# GT_16u2_Rev2.net
KiCad netlist of a schematic drawn in Altium Designer
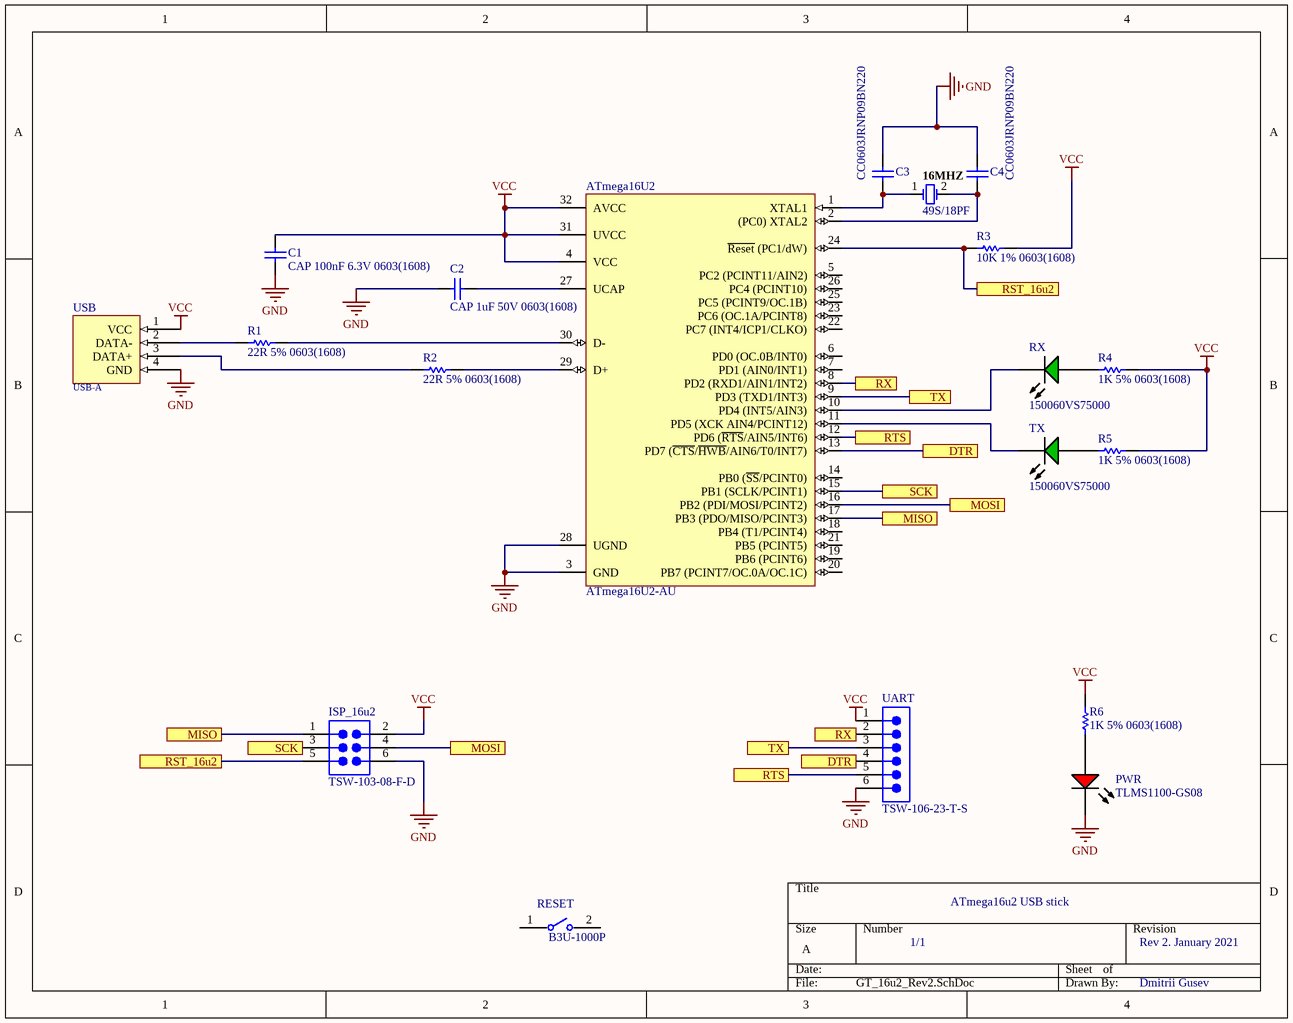
[diagram p0: GT_16u2_Rev2.SchDoc]

(export (version "E")
  (design (tool "Eeschema 10.0.6"))
  (components
    (comp (ref "16MHZ")
      (value "49S/18PF")
      (footprint "JPY-49S-18PF")
      (description "Crystal, 16 MHz, 18 pF, -20 to 70 degC, 2-Pin THD")
      (fields (field (name "MANUFACTURER") "Shenzhen Jingpengyuan"))
      (libsource (lib "Altium Content Vault") (part "XTAL-1-2-2"))
    )
    (comp (ref "ATmega16U2")
      (value "ATmega16U2-AU")
      (footprint "32A_M")
      (libsource (lib "Altium Content Vault") (part "MC-8B-ATM8U2-SQ32"))
    )
    (comp (ref "C1")
      (value "CAP 100nF 6.3V 0603(1608)")
      (footprint "CAPC0603(1608)100_L")
      (description "CAP 100nF 6.3V ±20% 0603 (1608 Metric) Thickness 1mm SMD")
      (fields (field (name "TOLERANCE") "Â±20%"))
      (libsource (lib "Altium Content Vault") (part "CAP"))
    )
    (comp (ref "C2")
      (value "CAP 1uF 50V 0603(1608)")
      (footprint "CAPC0603(1608)100_N")
      (description "CAP 1uF 50V ±20% 0603 (1608 Metric) Thickness 1mm SMD")
      (fields (field (name "TOLERANCE") "Â±20%"))
      (libsource (lib "Altium Content Vault") (part "CAP"))
    )
    (comp (ref "C3")
      (value "CC0603JRNP09BN220")
      (footprint "CAPC1608X90X40ML10T20")
      (description "Chip Capacitor, 22 pF, +/- 5%, 50 V, -55 to 125 degC, 0603 (1608 Metric), RoHS, Tape and Reel")
      (libsource (lib "Altium Content Vault") (part "CAP-NP-2"))
    )
    (comp (ref "C4")
      (value "CC0603JRNP09BN220")
      (footprint "CAPC1608X90X40ML10T20")
      (description "Chip Capacitor, 22 pF, +/- 5%, 50 V, -55 to 125 degC, 0603 (1608 Metric), RoHS, Tape and Reel")
      (libsource (lib "Altium Content Vault") (part "CAP-NP-2"))
    )
    (comp (ref "ISP_16u2")
      (value "TSW-103-08-F-D")
      (footprint "SMTC-TSW-103-08-X-D")
      (fields (field (name "MANUFACTURER") "Samtec"))
      (libsource (lib "Altium Content Vault") (part "SMTC-TSW-103-08-X-D"))
    )
    (comp (ref "PWR")
      (value "TLMS1100-GS08")
      (footprint "VISH-TLMX1100_V")
      (description "LED, RED, 2.1 V, -40 to 100 degC, 2-Pin SMD (0603), RoHS, Tape and Reel")
      (fields (field (name "TOLERANCE") "5%"))
      (libsource (lib "Altium Content Vault") (part "LED-RED-AK-2"))
    )
    (comp (ref "R1")
      (value "22R 5% 0603(1608)")
      (footprint "RESC0603(1608)_N")
      (description "22R 0.1W 5% 0603 (1608 Metric)  SMD")
      (fields (field (name "POWER") "0.1 W") (field (name "TOLERANCE") "5 %"))
      (libsource (lib "Altium Content Vault") (part "RES"))
    )
    (comp (ref "R2")
      (value "22R 5% 0603(1608)")
      (footprint "RESC0603(1608)_N")
      (description "22R 0.1W 5% 0603 (1608 Metric)  SMD")
      (fields (field (name "POWER") "0.1 W") (field (name "TOLERANCE") "5 %"))
      (libsource (lib "Altium Content Vault") (part "RES"))
    )
    (comp (ref "R3")
      (value "10K 1% 0603(1608)")
      (footprint "RESC0603(1608)_N")
      (description "10K 0.1W 1% 0603 (1608 Metric)  SMD")
      (fields (field (name "POWER") "0.1 W") (field (name "TOLERANCE") "1 %"))
      (libsource (lib "Altium Content Vault") (part "RES"))
    )
    (comp (ref "R4")
      (value "1K 5% 0603(1608)")
      (footprint "RESC0603(1608)_L")
      (description "1K 0.1W 5% 0603 (1608 Metric)  SMD")
      (fields (field (name "TOLERANCE") "5 %") (field (name "POWER") "0.1 W"))
      (libsource (lib "Altium Content Vault") (part "RES"))
    )
    (comp (ref "R5")
      (value "1K 5% 0603(1608)")
      (footprint "RESC0603(1608)_L")
      (description "1K 0.1W 5% 0603 (1608 Metric)  SMD")
      (fields (field (name "TOLERANCE") "5 %") (field (name "POWER") "0.1 W"))
      (libsource (lib "Altium Content Vault") (part "RES"))
    )
    (comp (ref "R6")
      (value "1K 5% 0603(1608)")
      (footprint "RESC0603(1608)_L")
      (description "1K 0.1W 5% 0603 (1608 Metric)  SMD")
      (fields (field (name "TOLERANCE") "5 %") (field (name "POWER") "0.1 W"))
      (libsource (lib "Altium Content Vault") (part "RES"))
    )
    (comp (ref "RESET")
      (value "B3U-1000P")
      (footprint "FP-B3U-1000P-MFG")
      (description "SWITCH TACTILE SPST-NO 0.05A 12V")
      (libsource (lib "Altium Content Vault") (part "ae622034201233ca1abcedc05908f33"))
    )
    (comp (ref "RX")
      (value "150060VS75000")
      (footprint "WE-150060VS75000_V")
      (libsource (lib "Altium Content Vault") (part "LED_GREEN_K1A2-2"))
    )
    (comp (ref "TX")
      (value "150060VS75000")
      (footprint "WE-150060VS75000_V")
      (libsource (lib "Altium Content Vault") (part "LED_GREEN_K1A2-2"))
    )
    (comp (ref "UART")
      (value "TSW-106-23-T-S")
      (footprint "SMTC-TSW-106-23-X-S")
      (fields (field (name "MANUFACTURER") "Samtec"))
      (libsource (lib "Altium Content Vault") (part "SMTC-TSW-106-X-X-S-X"))
    )
    (comp (ref "USB") (value "USB-A") (footprint "USB A") (libsource (lib "MSE310_PID") (part "USB-A")))
  )
  (nets
    (net (code "1") (name "/DTR") (class "Default")
      (node (ref "ATmega16U2") (pin "13") (pinfunction "PD7_(~{CTS}/~{HWB}/AIN6/T0/INT7)_13") (pintype "bidirectional"))
      (node (ref "UART") (pin "4") (pinfunction "4_4") (pintype "passive"))
    )
    (net (code "2") (name "/MISO") (class "Default")
      (node (ref "ATmega16U2") (pin "17") (pinfunction "PB3_(PDO/MISO/PCINT3)_17") (pintype "bidirectional"))
      (node (ref "ISP_16u2") (pin "1") (pinfunction "1_1") (pintype "passive"))
    )
    (net (code "3") (name "/MOSI") (class "Default")
      (node (ref "ATmega16U2") (pin "16") (pinfunction "PB2_(PDI/MOSI/PCINT2)_16") (pintype "bidirectional"))
      (node (ref "ISP_16u2") (pin "4") (pinfunction "4_4") (pintype "passive"))
    )
    (net (code "4") (name "/RST_16u2") (class "Default")
      (node (ref "ATmega16U2") (pin "24") (pinfunction "~{Reset}_(PC1/dW)_24") (pintype "bidirectional"))
      (node (ref "ISP_16u2") (pin "5") (pinfunction "5_5") (pintype "passive"))
      (node (ref "R3") (pin "1") (pinfunction "1_1") (pintype "passive"))
    )
    (net (code "5") (name "/RTS") (class "Default")
      (node (ref "ATmega16U2") (pin "12") (pinfunction "PD6_(~{RTS}/AIN5/INT6)_12") (pintype "bidirectional"))
      (node (ref "UART") (pin "5") (pinfunction "5_5") (pintype "passive"))
    )
    (net (code "6") (name "/RX") (class "Default")
      (node (ref "ATmega16U2") (pin "8") (pinfunction "PD2_(RXD1/AIN1/INT2)_8") (pintype "bidirectional"))
      (node (ref "UART") (pin "2") (pinfunction "2_2") (pintype "passive"))
    )
    (net (code "7") (name "/SCK") (class "Default")
      (node (ref "ATmega16U2") (pin "15") (pinfunction "PB1_(SCLK/PCINT1)_15") (pintype "bidirectional"))
      (node (ref "ISP_16u2") (pin "3") (pinfunction "3_3") (pintype "passive"))
    )
    (net (code "8") (name "/TX") (class "Default")
      (node (ref "ATmega16U2") (pin "9") (pinfunction "PD3_(TXD1/INT3)_9") (pintype "bidirectional"))
      (node (ref "UART") (pin "3") (pinfunction "3_3") (pintype "passive"))
    )
    (net (code "9") (name "GND") (class "Default")
      (node (ref "ATmega16U2") (pin "28") (pinfunction "UGND_28") (pintype "power_in"))
      (node (ref "ATmega16U2") (pin "3") (pinfunction "GND_3") (pintype "power_in"))
      (node (ref "C1") (pin "1") (pinfunction "1_1") (pintype "passive"))
      (node (ref "C2") (pin "1") (pinfunction "1_1") (pintype "passive"))
      (node (ref "C3") (pin "2") (pinfunction "2_2") (pintype "passive"))
      (node (ref "C4") (pin "2") (pinfunction "2_2") (pintype "passive"))
      (node (ref "ISP_16u2") (pin "6") (pinfunction "6_6") (pintype "passive"))
      (node (ref "PWR") (pin "2") (pinfunction "K_2") (pintype "passive"))
      (node (ref "UART") (pin "6") (pinfunction "6_6") (pintype "passive"))
      (node (ref "USB") (pin "4") (pinfunction "GND_4") (pintype "input"))
    )
    (net (code "10") (name "Net-(ATmega16U2-(PC0)_XTAL2)") (class "Default")
      (node (ref "16MHZ") (pin "2") (pinfunction "2_2") (pintype "passive"))
      (node (ref "ATmega16U2") (pin "2") (pinfunction "(PC0)_XTAL2_2") (pintype "bidirectional"))
      (node (ref "C4") (pin "1") (pinfunction "1_1") (pintype "passive"))
    )
    (net (code "11") (name "Net-(ATmega16U2-D+)") (class "Default")
      (node (ref "ATmega16U2") (pin "29") (pinfunction "D+_29") (pintype "bidirectional"))
      (node (ref "R2") (pin "2") (pinfunction "2_2") (pintype "passive"))
    )
    (net (code "12") (name "Net-(ATmega16U2-D-)") (class "Default")
      (node (ref "ATmega16U2") (pin "30") (pinfunction "D-_30") (pintype "bidirectional"))
      (node (ref "R1") (pin "2") (pinfunction "2_2") (pintype "passive"))
    )
    (net (code "13") (name "Net-(ATmega16U2-PD4_(INT5{slash}AIN3))") (class "Default")
      (node (ref "ATmega16U2") (pin "10") (pinfunction "PD4_(INT5/AIN3)_10") (pintype "bidirectional"))
      (node (ref "RX") (pin "1") (pinfunction "K_1") (pintype "passive"))
    )
    (net (code "14") (name "Net-(ATmega16U2-PD5_(XCK_AIN4{slash}PCINT12))") (class "Default")
      (node (ref "ATmega16U2") (pin "11") (pinfunction "PD5_(XCK_AIN4/PCINT12)_11") (pintype "bidirectional"))
      (node (ref "TX") (pin "1") (pinfunction "K_1") (pintype "passive"))
    )
    (net (code "15") (name "Net-(ATmega16U2-UCAP)") (class "Default")
      (node (ref "ATmega16U2") (pin "27") (pinfunction "UCAP_27") (pintype "power_in"))
      (node (ref "C2") (pin "2") (pinfunction "2_2") (pintype "passive"))
    )
    (net (code "16") (name "Net-(ATmega16U2-XTAL1)") (class "Default")
      (node (ref "16MHZ") (pin "1") (pinfunction "1_1") (pintype "passive"))
      (node (ref "ATmega16U2") (pin "1") (pinfunction "XTAL1_1") (pintype "input"))
      (node (ref "C3") (pin "1") (pinfunction "1_1") (pintype "passive"))
    )
    (net (code "17") (name "Net-(PWR-A)") (class "Default")
      (node (ref "PWR") (pin "1") (pinfunction "A_1") (pintype "passive"))
      (node (ref "R6") (pin "1") (pinfunction "1_1") (pintype "passive"))
    )
    (net (code "18") (name "Net-(RX-A)") (class "Default")
      (node (ref "R4") (pin "1") (pinfunction "1_1") (pintype "passive"))
      (node (ref "RX") (pin "2") (pinfunction "A_2") (pintype "passive"))
    )
    (net (code "19") (name "Net-(TX-A)") (class "Default")
      (node (ref "R5") (pin "1") (pinfunction "1_1") (pintype "passive"))
      (node (ref "TX") (pin "2") (pinfunction "A_2") (pintype "passive"))
    )
    (net (code "20") (name "Net-(USB-DATA+)") (class "Default")
      (node (ref "R2") (pin "1") (pinfunction "1_1") (pintype "passive"))
      (node (ref "USB") (pin "3") (pinfunction "DATA+_3") (pintype "input"))
    )
    (net (code "21") (name "Net-(USB-DATA-)") (class "Default")
      (node (ref "R1") (pin "1") (pinfunction "1_1") (pintype "passive"))
      (node (ref "USB") (pin "2") (pinfunction "DATA-_2") (pintype "input"))
    )
    (net (code "22") (name "VCC") (class "Default")
      (node (ref "ATmega16U2") (pin "31") (pinfunction "UVCC_31") (pintype "power_in"))
      (node (ref "ATmega16U2") (pin "32") (pinfunction "AVCC_32") (pintype "power_in"))
      (node (ref "ATmega16U2") (pin "4") (pinfunction "VCC_4") (pintype "power_in"))
      (node (ref "C1") (pin "2") (pinfunction "2_2") (pintype "passive"))
      (node (ref "ISP_16u2") (pin "2") (pinfunction "2_2") (pintype "passive"))
      (node (ref "R3") (pin "2") (pinfunction "2_2") (pintype "passive"))
      (node (ref "R4") (pin "2") (pinfunction "2_2") (pintype "passive"))
      (node (ref "R5") (pin "2") (pinfunction "2_2") (pintype "passive"))
      (node (ref "R6") (pin "2") (pinfunction "2_2") (pintype "passive"))
      (node (ref "UART") (pin "1") (pinfunction "1_1") (pintype "passive"))
      (node (ref "USB") (pin "1") (pinfunction "VCC_1") (pintype "input"))
    )
    (net (code "23") (name "unconnected-(ATmega16U2-PB0_(~{SS}{slash}PCINT0)-Pad14)") (class "Default")
      (node (ref "ATmega16U2") (pin "14") (pinfunction "PB0_(~{SS}/PCINT0)_14") (pintype "bidirectional"))
    )
    (net (code "24") (name "unconnected-(ATmega16U2-PB4_(T1{slash}PCINT4)-Pad18)") (class "Default")
      (node (ref "ATmega16U2") (pin "18") (pinfunction "PB4_(T1/PCINT4)_18") (pintype "bidirectional"))
    )
    (net (code "25") (name "unconnected-(ATmega16U2-PB5_(PCINT5)-Pad21)") (class "Default")
      (node (ref "ATmega16U2") (pin "21") (pinfunction "PB5_(PCINT5)_21") (pintype "bidirectional"))
    )
    (net (code "26") (name "unconnected-(ATmega16U2-PB6_(PCINT6)-Pad19)") (class "Default")
      (node (ref "ATmega16U2") (pin "19") (pinfunction "PB6_(PCINT6)_19") (pintype "bidirectional"))
    )
    (net (code "27") (name "unconnected-(ATmega16U2-PB7_(PCINT7{slash}OC.0A{slash}OC.1C)-Pad20)") (class "Default")
      (node (ref "ATmega16U2") (pin "20") (pinfunction "PB7_(PCINT7/OC.0A/OC.1C)_20") (pintype "bidirectional"))
    )
    (net (code "28") (name "unconnected-(ATmega16U2-PC2_(PCINT11{slash}AIN2)-Pad5)") (class "Default")
      (node (ref "ATmega16U2") (pin "5") (pinfunction "PC2_(PCINT11/AIN2)_5") (pintype "bidirectional"))
    )
    (net (code "29") (name "unconnected-(ATmega16U2-PC4_(PCINT10)-Pad26)") (class "Default")
      (node (ref "ATmega16U2") (pin "26") (pinfunction "PC4_(PCINT10)_26") (pintype "bidirectional"))
    )
    (net (code "30") (name "unconnected-(ATmega16U2-PC5_(PCINT9{slash}OC.1B)-Pad25)") (class "Default")
      (node (ref "ATmega16U2") (pin "25") (pinfunction "PC5_(PCINT9/OC.1B)_25") (pintype "bidirectional"))
    )
    (net (code "31") (name "unconnected-(ATmega16U2-PC6_(OC.1A{slash}PCINT8)-Pad23)") (class "Default")
      (node (ref "ATmega16U2") (pin "23") (pinfunction "PC6_(OC.1A/PCINT8)_23") (pintype "bidirectional"))
    )
    (net (code "32") (name "unconnected-(ATmega16U2-PC7_(INT4{slash}ICP1{slash}CLKO)-Pad22)") (class "Default")
      (node (ref "ATmega16U2") (pin "22") (pinfunction "PC7_(INT4/ICP1/CLKO)_22") (pintype "bidirectional"))
    )
    (net (code "33") (name "unconnected-(ATmega16U2-PD0_(OC.0B{slash}INT0)-Pad6)") (class "Default")
      (node (ref "ATmega16U2") (pin "6") (pinfunction "PD0_(OC.0B/INT0)_6") (pintype "bidirectional"))
    )
    (net (code "34") (name "unconnected-(ATmega16U2-PD1_(AIN0{slash}INT1)-Pad7)") (class "Default")
      (node (ref "ATmega16U2") (pin "7") (pinfunction "PD1_(AIN0/INT1)_7") (pintype "bidirectional"))
    )
    (net (code "35") (name "unconnected-(RESET-Pad1)") (class "Default")
      (node (ref "RESET") (pin "1") (pinfunction "1_1") (pintype "passive"))
    )
    (net (code "36") (name "unconnected-(RESET-Pad2)") (class "Default")
      (node (ref "RESET") (pin "2") (pinfunction "2_2") (pintype "passive"))
    )
  )
)
